# ip_phone_e_wifi.net
KiCad netlist of a schematic drawn in Altium Designer
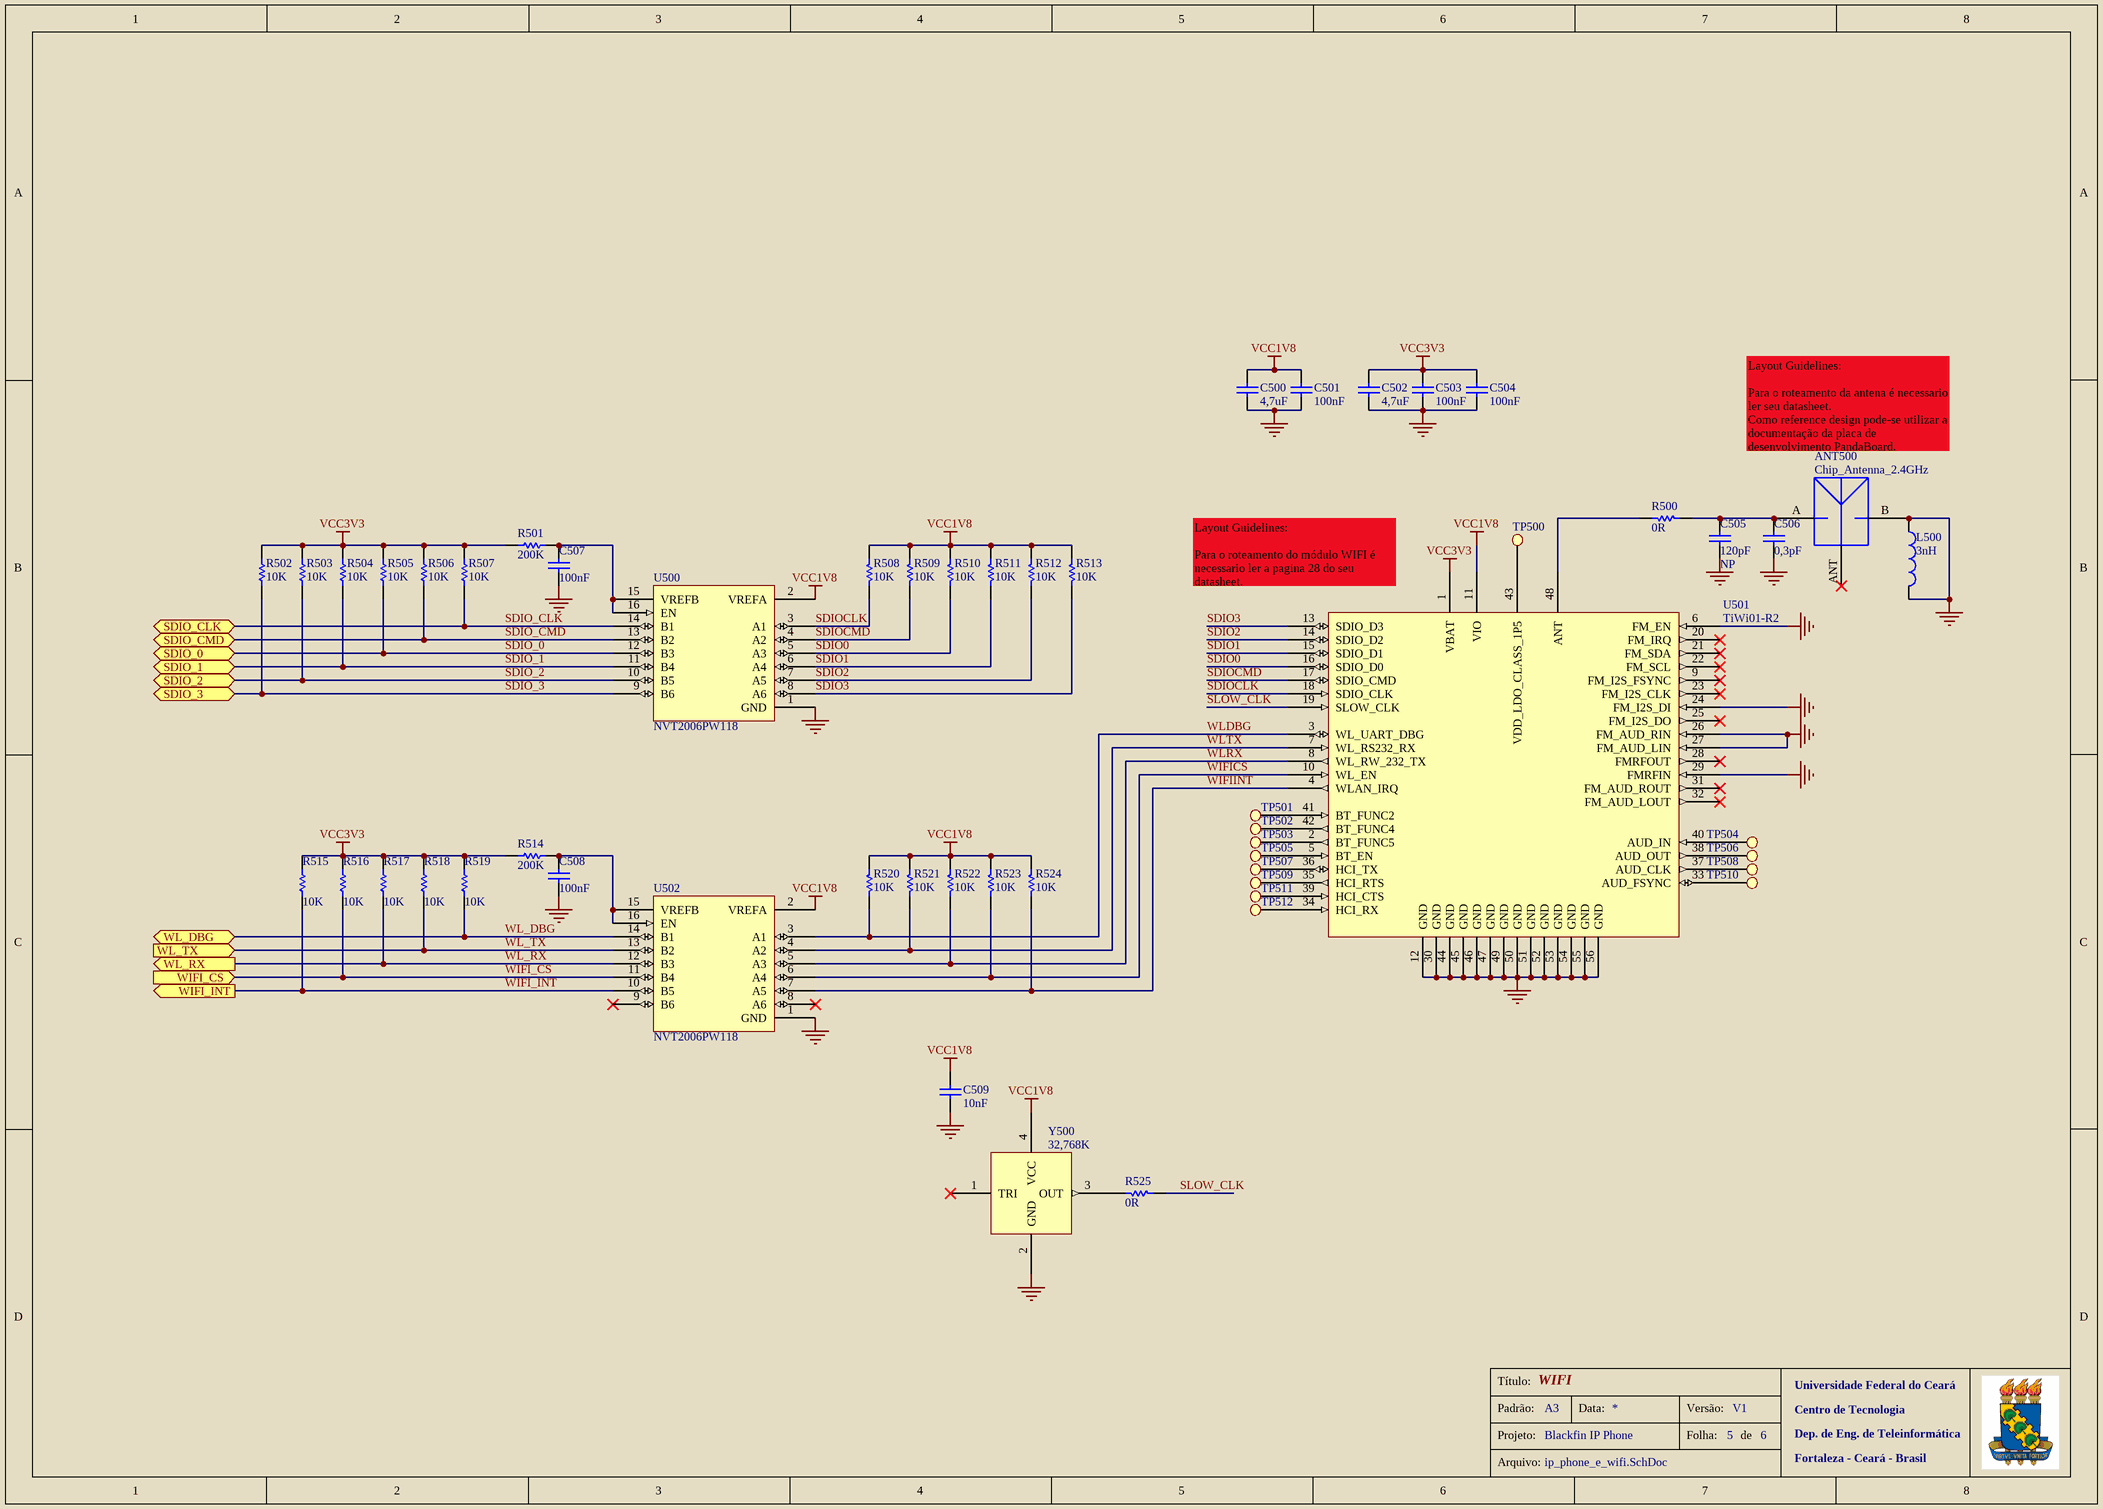
[diagram p0: ip_phone_e_wifi.SchDoc]

(export (version "E")
  (design (tool "Eeschema 10.0.6"))
  (components
    (comp (ref "ANT500")
      (value "Chip_Antenna_2.4GHz")
      (footprint "ip_phone:ANTENNA")
      (description "Antenna 2.4GHz Ceramic Chip SMD")
      (fields (field (name "MANUFACTURER") "TDK") (field (name "EVENDORPART#") "445-6134-1-ND"))
      (libsource (lib "ip_phone") (part "Antenna2_4GHzChip"))
    )
    (comp (ref "C500")
      (value "4,7uF")
      (footprint "ip_phone:CC1005-0402")
      (description "MLCC - SMD/SMT 4.7uF 20% 6.3Volts 0402")
      (fields (field (name "EVENDORPART#") "810-C1005X5R0J475M") (field (name "MANUFACTURER") "TDK"))
      (libsource (lib "ip_phone") (part "Capacitor"))
    )
    (comp (ref "C501")
      (value "100nF")
      (footprint "ip_phone:CC1005-0402")
      (description "MLCC - SMD/SMT 0.1UF 16V 10% 0402")
      (fields (field (name "EVENDORPART#") "810-C1005X7R1C104K") (field (name "MANUFACTURER") "TDK"))
      (libsource (lib "ip_phone") (part "Capacitor"))
    )
    (comp (ref "C502")
      (value "4,7uF")
      (footprint "ip_phone:CC1005-0402")
      (description "MLCC - SMD/SMT 4.7uF 20% 6.3Volts 0402")
      (fields (field (name "EVENDORPART#") "810-C1005X5R0J475M") (field (name "MANUFACTURER") "TDK"))
      (libsource (lib "ip_phone") (part "Capacitor"))
    )
    (comp (ref "C503")
      (value "100nF")
      (footprint "ip_phone:CC1005-0402")
      (description "MLCC - SMD/SMT 0.1UF 16V 10% 0402")
      (fields (field (name "EVENDORPART#") "810-C1005X7R1C104K") (field (name "MANUFACTURER") "TDK"))
      (libsource (lib "ip_phone") (part "Capacitor"))
    )
    (comp (ref "C504")
      (value "100nF")
      (footprint "ip_phone:CC1005-0402")
      (description "MLCC - SMD/SMT 0.1UF 16V 10% 0402")
      (fields (field (name "EVENDORPART#") "810-C1005X7R1C104K") (field (name "MANUFACTURER") "TDK"))
      (libsource (lib "ip_phone") (part "Capacitor"))
    )
    (comp (ref "C505")
      (value "120pF")
      (footprint "ip_phone:CC1005-0402_NP")
      (description "MLCC - SMD/SMT 0402 120pF 50volts C0G 5%")
      (fields
        (field (name "EVENDORPART#") "810-C1005C0G1H121J")
        (field (name "MANUFACTURER") "TDK")
        (field (name "NP") "NP")
      )
      (libsource (lib "ip_phone") (part "Capacitor"))
    )
    (comp (ref "C506")
      (value "0,3pF")
      (footprint "ip_phone:CC1005-0402")
      (description "MLCC - SMD/SMT 0.3pF 50Volts C0G 0.1pF")
      (fields (field (name "EVENDORPART#") "81-GRM1535C1HR30BD5D") (field (name "MANUFACTURER") "Murata"))
      (libsource (lib "ip_phone") (part "Capacitor"))
    )
    (comp (ref "C507")
      (value "100nF")
      (footprint "ip_phone:CC1005-0402")
      (description "MLCC - SMD/SMT 0.1UF 16V 10% 0402")
      (fields (field (name "EVENDORPART#") "810-C1005X7R1C104K") (field (name "MANUFACTURER") "TDK"))
      (libsource (lib "ip_phone") (part "Capacitor"))
    )
    (comp (ref "C508")
      (value "100nF")
      (footprint "ip_phone:CC1005-0402")
      (description "MLCC - SMD/SMT 0.1UF 16V 10% 0402")
      (fields (field (name "EVENDORPART#") "810-C1005X7R1C104K") (field (name "MANUFACTURER") "TDK"))
      (libsource (lib "ip_phone") (part "Capacitor"))
    )
    (comp (ref "C509")
      (value "10nF")
      (footprint "ip_phone:CC1005-0402")
      (description "Ceramic Capacitor 10nF 50V X7R 0402")
      (fields (field (name "EVENDORPART#") "810-C1005X7R1C103K") (field (name "MANUFACTURER") "TDK"))
      (libsource (lib "ip_phone") (part "Capacitor"))
    )
    (comp (ref "L500")
      (value "3nH")
      (footprint "ip_phone:INDUTOR_0402")
      (description "Inductor")
      (fields
        (field (name "EVENDORPART#") "712-1457-1-ND")
        (field (name "MANUFACTURER") "Johanson Technology Inc")
      )
      (libsource (lib "ip_phone") (part "Inductor"))
    )
    (comp (ref "R500")
      (value "0R")
      (footprint "ip_phone:CR1005-0402")
      (description "Thick Film Resistors 0402 1/16W Jumper")
      (fields
        (field (name "EVENDORPART#") "667-ERJ-2GE0R00X")
        (field (name "MANUFACTURER") "Panasonic Electronic Components")
      )
      (libsource (lib "ip_phone") (part "Resistor"))
    )
    (comp (ref "R501")
      (value "200K")
      (footprint "ip_phone:CR1005-0402")
      (description "Thick Film Resistors 1/16WATT 200K 0402")
      (fields (field (name "EVENDORPART#") "304-200K-RC") (field (name "MANUFACTURER") "Xicon"))
      (libsource (lib "ip_phone") (part "Resistor"))
    )
    (comp (ref "R502")
      (value "10K")
      (footprint "ip_phone:CR1005-0402")
      (description "Thick Film Resistors SMD 0402 10K 5%  1/16 W")
      (fields (field (name "EVENDORPART#") "311-10KJRCT-ND") (field (name "MANUFACTURER") "Yageo"))
      (libsource (lib "ip_phone") (part "Resistor"))
    )
    (comp (ref "R503")
      (value "10K")
      (footprint "ip_phone:CR1005-0402")
      (description "Thick Film Resistors SMD 0402 10K 5%  1/16 W")
      (fields (field (name "EVENDORPART#") "311-10KJRCT-ND") (field (name "MANUFACTURER") "Yageo"))
      (libsource (lib "ip_phone") (part "Resistor"))
    )
    (comp (ref "R504")
      (value "10K")
      (footprint "ip_phone:CR1005-0402")
      (description "Thick Film Resistors SMD 0402 10K 5%  1/16 W")
      (fields (field (name "EVENDORPART#") "311-10KJRCT-ND") (field (name "MANUFACTURER") "Yageo"))
      (libsource (lib "ip_phone") (part "Resistor"))
    )
    (comp (ref "R505")
      (value "10K")
      (footprint "ip_phone:CR1005-0402")
      (description "Thick Film Resistors SMD 0402 10K 5%  1/16 W")
      (fields (field (name "EVENDORPART#") "311-10KJRCT-ND") (field (name "MANUFACTURER") "Yageo"))
      (libsource (lib "ip_phone") (part "Resistor"))
    )
    (comp (ref "R506")
      (value "10K")
      (footprint "ip_phone:CR1005-0402")
      (description "Thick Film Resistors SMD 0402 10K 5%  1/16 W")
      (fields (field (name "EVENDORPART#") "311-10KJRCT-ND") (field (name "MANUFACTURER") "Yageo"))
      (libsource (lib "ip_phone") (part "Resistor"))
    )
    (comp (ref "R507")
      (value "10K")
      (footprint "ip_phone:CR1005-0402")
      (description "Thick Film Resistors SMD 0402 10K 5%  1/16 W")
      (fields (field (name "EVENDORPART#") "311-10KJRCT-ND") (field (name "MANUFACTURER") "Yageo"))
      (libsource (lib "ip_phone") (part "Resistor"))
    )
    (comp (ref "R508")
      (value "10K")
      (footprint "ip_phone:CR1005-0402")
      (description "Thick Film Resistors SMD 0402 10K 5%  1/16 W")
      (fields (field (name "EVENDORPART#") "311-10KJRCT-ND") (field (name "MANUFACTURER") "Yageo"))
      (libsource (lib "ip_phone") (part "Resistor"))
    )
    (comp (ref "R509")
      (value "10K")
      (footprint "ip_phone:CR1005-0402")
      (description "Thick Film Resistors SMD 0402 10K 5%  1/16 W")
      (fields (field (name "EVENDORPART#") "311-10KJRCT-ND") (field (name "MANUFACTURER") "Yageo"))
      (libsource (lib "ip_phone") (part "Resistor"))
    )
    (comp (ref "R510")
      (value "10K")
      (footprint "ip_phone:CR1005-0402")
      (description "Thick Film Resistors SMD 0402 10K 5%  1/16 W")
      (fields (field (name "EVENDORPART#") "311-10KJRCT-ND") (field (name "MANUFACTURER") "Yageo"))
      (libsource (lib "ip_phone") (part "Resistor"))
    )
    (comp (ref "R511")
      (value "10K")
      (footprint "ip_phone:CR1005-0402")
      (description "Thick Film Resistors SMD 0402 10K 5%  1/16 W")
      (fields (field (name "EVENDORPART#") "311-10KJRCT-ND") (field (name "MANUFACTURER") "Yageo"))
      (libsource (lib "ip_phone") (part "Resistor"))
    )
    (comp (ref "R512")
      (value "10K")
      (footprint "ip_phone:CR1005-0402")
      (description "Thick Film Resistors SMD 0402 10K 5%  1/16 W")
      (fields (field (name "EVENDORPART#") "311-10KJRCT-ND") (field (name "MANUFACTURER") "Yageo"))
      (libsource (lib "ip_phone") (part "Resistor"))
    )
    (comp (ref "R513")
      (value "10K")
      (footprint "ip_phone:CR1005-0402")
      (description "Thick Film Resistors SMD 0402 10K 5%  1/16 W")
      (fields (field (name "EVENDORPART#") "311-10KJRCT-ND") (field (name "MANUFACTURER") "Yageo"))
      (libsource (lib "ip_phone") (part "Resistor"))
    )
    (comp (ref "R514")
      (value "200K")
      (footprint "ip_phone:CR1005-0402")
      (description "Thick Film Resistors 1/16WATT 200K 0402")
      (fields (field (name "EVENDORPART#") "304-200K-RC") (field (name "MANUFACTURER") "Xicon"))
      (libsource (lib "ip_phone") (part "Resistor"))
    )
    (comp (ref "R515")
      (value "10K")
      (footprint "ip_phone:CR1005-0402")
      (description "Thick Film Resistors SMD 0402 10K 5%  1/16 W")
      (fields (field (name "EVENDORPART#") "311-10KJRCT-ND") (field (name "MANUFACTURER") "Yageo"))
      (libsource (lib "ip_phone") (part "Resistor"))
    )
    (comp (ref "R516")
      (value "10K")
      (footprint "ip_phone:CR1005-0402")
      (description "Thick Film Resistors SMD 0402 10K 5%  1/16 W")
      (fields (field (name "EVENDORPART#") "311-10KJRCT-ND") (field (name "MANUFACTURER") "Yageo"))
      (libsource (lib "ip_phone") (part "Resistor"))
    )
    (comp (ref "R517")
      (value "10K")
      (footprint "ip_phone:CR1005-0402")
      (description "Thick Film Resistors SMD 0402 10K 5%  1/16 W")
      (fields (field (name "EVENDORPART#") "311-10KJRCT-ND") (field (name "MANUFACTURER") "Yageo"))
      (libsource (lib "ip_phone") (part "Resistor"))
    )
    (comp (ref "R518")
      (value "10K")
      (footprint "ip_phone:CR1005-0402")
      (description "Thick Film Resistors SMD 0402 10K 5%  1/16 W")
      (fields (field (name "EVENDORPART#") "311-10KJRCT-ND") (field (name "MANUFACTURER") "Yageo"))
      (libsource (lib "ip_phone") (part "Resistor"))
    )
    (comp (ref "R519")
      (value "10K")
      (footprint "ip_phone:CR1005-0402")
      (description "Thick Film Resistors SMD 0402 10K 5%  1/16 W")
      (fields (field (name "EVENDORPART#") "311-10KJRCT-ND") (field (name "MANUFACTURER") "Yageo"))
      (libsource (lib "ip_phone") (part "Resistor"))
    )
    (comp (ref "R520")
      (value "10K")
      (footprint "ip_phone:CR1005-0402")
      (description "Thick Film Resistors SMD 0402 10K 5%  1/16 W")
      (fields (field (name "EVENDORPART#") "311-10KJRCT-ND") (field (name "MANUFACTURER") "Yageo"))
      (libsource (lib "ip_phone") (part "Resistor"))
    )
    (comp (ref "R521")
      (value "10K")
      (footprint "ip_phone:CR1005-0402")
      (description "Thick Film Resistors SMD 0402 10K 5%  1/16 W")
      (fields (field (name "EVENDORPART#") "311-10KJRCT-ND") (field (name "MANUFACTURER") "Yageo"))
      (libsource (lib "ip_phone") (part "Resistor"))
    )
    (comp (ref "R522")
      (value "10K")
      (footprint "ip_phone:CR1005-0402")
      (description "Thick Film Resistors SMD 0402 10K 5%  1/16 W")
      (fields (field (name "EVENDORPART#") "311-10KJRCT-ND") (field (name "MANUFACTURER") "Yageo"))
      (libsource (lib "ip_phone") (part "Resistor"))
    )
    (comp (ref "R523")
      (value "10K")
      (footprint "ip_phone:CR1005-0402")
      (description "Thick Film Resistors SMD 0402 10K 5%  1/16 W")
      (fields (field (name "EVENDORPART#") "311-10KJRCT-ND") (field (name "MANUFACTURER") "Yageo"))
      (libsource (lib "ip_phone") (part "Resistor"))
    )
    (comp (ref "R524")
      (value "10K")
      (footprint "ip_phone:CR1005-0402")
      (description "Thick Film Resistors SMD 0402 10K 5%  1/16 W")
      (fields (field (name "EVENDORPART#") "311-10KJRCT-ND") (field (name "MANUFACTURER") "Yageo"))
      (libsource (lib "ip_phone") (part "Resistor"))
    )
    (comp (ref "R525")
      (value "0R")
      (footprint "ip_phone:CR1005-0402")
      (description "Thick Film Resistors 0402 1/16W Jumper")
      (fields
        (field (name "EVENDORPART#") "667-ERJ-2GE0R00X")
        (field (name "MANUFACTURER") "Panasonic Electronic Components")
      )
      (libsource (lib "ip_phone") (part "Resistor"))
    )
    (comp (ref "TP500")
      (value "Test Point")
      (footprint "ip_phone:Test Point")
      (fields (field (name "EVENDORPART#") "NÃO SE APLICA"))
      (libsource (lib "ip_phone") (part "Test Point"))
    )
    (comp (ref "TP501")
      (value "Test Point")
      (footprint "ip_phone:Test Point")
      (fields (field (name "EVENDORPART#") "NÃO SE APLICA"))
      (libsource (lib "ip_phone") (part "Test Point"))
    )
    (comp (ref "TP502")
      (value "Test Point")
      (footprint "ip_phone:Test Point")
      (fields (field (name "EVENDORPART#") "NÃO SE APLICA"))
      (libsource (lib "ip_phone") (part "Test Point"))
    )
    (comp (ref "TP503")
      (value "Test Point")
      (footprint "ip_phone:Test Point")
      (fields (field (name "EVENDORPART#") "NÃO SE APLICA"))
      (libsource (lib "ip_phone") (part "Test Point"))
    )
    (comp (ref "TP504")
      (value "Test Point")
      (footprint "ip_phone:Test Point")
      (fields (field (name "EVENDORPART#") "NÃO SE APLICA"))
      (libsource (lib "ip_phone") (part "Test Point"))
    )
    (comp (ref "TP505")
      (value "Test Point")
      (footprint "ip_phone:Test Point")
      (fields (field (name "EVENDORPART#") "NÃO SE APLICA"))
      (libsource (lib "ip_phone") (part "Test Point"))
    )
    (comp (ref "TP506")
      (value "Test Point")
      (footprint "ip_phone:Test Point")
      (fields (field (name "EVENDORPART#") "NÃO SE APLICA"))
      (libsource (lib "ip_phone") (part "Test Point"))
    )
    (comp (ref "TP507")
      (value "Test Point")
      (footprint "ip_phone:Test Point")
      (fields (field (name "EVENDORPART#") "NÃO SE APLICA"))
      (libsource (lib "ip_phone") (part "Test Point"))
    )
    (comp (ref "TP508")
      (value "Test Point")
      (footprint "ip_phone:Test Point")
      (fields (field (name "EVENDORPART#") "NÃO SE APLICA"))
      (libsource (lib "ip_phone") (part "Test Point"))
    )
    (comp (ref "TP509")
      (value "Test Point")
      (footprint "ip_phone:Test Point")
      (fields (field (name "EVENDORPART#") "NÃO SE APLICA"))
      (libsource (lib "ip_phone") (part "Test Point"))
    )
    (comp (ref "TP510")
      (value "Test Point")
      (footprint "ip_phone:Test Point")
      (fields (field (name "EVENDORPART#") "NÃO SE APLICA"))
      (libsource (lib "ip_phone") (part "Test Point"))
    )
    (comp (ref "TP511")
      (value "Test Point")
      (footprint "ip_phone:Test Point")
      (fields (field (name "EVENDORPART#") "NÃO SE APLICA"))
      (libsource (lib "ip_phone") (part "Test Point"))
    )
    (comp (ref "TP512")
      (value "Test Point")
      (footprint "ip_phone:Test Point")
      (fields (field (name "EVENDORPART#") "NÃO SE APLICA"))
      (libsource (lib "ip_phone") (part "Test Point"))
    )
    (comp (ref "U500")
      (value "NVT2006PW118")
      (footprint "ip_phone:TSSOP16")
      (description "Translation - Voltage Levels +/-50mA 1.5ns 2.1-5V")
      (fields
        (field (name "EVENDORPART#") "771-NVT2006PW118")
        (field (name "MANUFACTURER") "NXP Semiconductors")
      )
      (libsource (lib "ip_phone") (part "NVT2006PW118"))
    )
    (comp (ref "U501")
      (value "TiWi01-R2")
      (footprint "ip_phone:WIFI_MODULE")
      (description "WiFi / 802.11 TiWi01-R2 Module with U.FL Connector")
      (fields (field (name "EVENDORPART#") "741-450-0037") (field (name "MANUFACTURER") "LS Research"))
      (libsource (lib "ip_phone") (part "TiWi01-R2"))
    )
    (comp (ref "U502")
      (value "NVT2006PW118")
      (footprint "ip_phone:TSSOP16")
      (description "Translation - Voltage Levels +/-50mA 1.5ns 2.1-5V")
      (fields
        (field (name "EVENDORPART#") "771-NVT2006PW118")
        (field (name "MANUFACTURER") "NXP Semiconductors")
      )
      (libsource (lib "ip_phone") (part "NVT2006PW118"))
    )
    (comp (ref "Y500")
      (value "32,768K")
      (footprint "ip_phone:OSCILLATOR_32K")
      (description "Standard Clock Oscillators 32.768KHz 1.8V -40C +85C 25ppm")
      (fields (field (name "EVENDORPART#") "815-ASEK2-32.7K-LRT") (field (name "MANUFACTURER") "Abracon"))
      (libsource (lib "ip_phone") (part "Oscillator_32K"))
    )
  )
  (nets
    (net (code "1") (name "/SDIO0") (class "Default")
      (node (ref "R510") (pin "1") (pinfunction "1_1") (pintype "passive"))
      (node (ref "U500") (pin "5") (pinfunction "A3_5") (pintype "bidirectional"))
      (node (ref "U501") (pin "16") (pinfunction "SDIO_D0_16") (pintype "bidirectional"))
    )
    (net (code "2") (name "/SDIO1") (class "Default")
      (node (ref "R511") (pin "1") (pinfunction "1_1") (pintype "passive"))
      (node (ref "U500") (pin "6") (pinfunction "A4_6") (pintype "bidirectional"))
      (node (ref "U501") (pin "15") (pinfunction "SDIO_D1_15") (pintype "bidirectional"))
    )
    (net (code "3") (name "/SDIO2") (class "Default")
      (node (ref "R512") (pin "1") (pinfunction "1_1") (pintype "passive"))
      (node (ref "U500") (pin "7") (pinfunction "A5_7") (pintype "bidirectional"))
      (node (ref "U501") (pin "14") (pinfunction "SDIO_D2_14") (pintype "bidirectional"))
    )
    (net (code "4") (name "/SDIO3") (class "Default")
      (node (ref "R513") (pin "1") (pinfunction "1_1") (pintype "passive"))
      (node (ref "U500") (pin "8") (pinfunction "A6_8") (pintype "bidirectional"))
      (node (ref "U501") (pin "13") (pinfunction "SDIO_D3_13") (pintype "bidirectional"))
    )
    (net (code "5") (name "/SDIOCLK") (class "Default")
      (node (ref "R508") (pin "1") (pinfunction "1_1") (pintype "passive"))
      (node (ref "U500") (pin "3") (pinfunction "A1_3") (pintype "bidirectional"))
      (node (ref "U501") (pin "18") (pinfunction "SDIO_CLK_18") (pintype "input"))
    )
    (net (code "6") (name "/SDIOCMD") (class "Default")
      (node (ref "R509") (pin "1") (pinfunction "1_1") (pintype "passive"))
      (node (ref "U500") (pin "4") (pinfunction "A2_4") (pintype "bidirectional"))
      (node (ref "U501") (pin "17") (pinfunction "SDIO_CMD_17") (pintype "bidirectional"))
    )
    (net (code "7") (name "/SDIO_0") (class "Default")
      (node (ref "R505") (pin "2") (pinfunction "2_2") (pintype "passive"))
      (node (ref "U500") (pin "12") (pinfunction "B3_12") (pintype "bidirectional"))
    )
    (net (code "8") (name "/SDIO_1") (class "Default")
      (node (ref "R504") (pin "2") (pinfunction "2_2") (pintype "passive"))
      (node (ref "U500") (pin "11") (pinfunction "B4_11") (pintype "bidirectional"))
    )
    (net (code "9") (name "/SDIO_2") (class "Default")
      (node (ref "R503") (pin "2") (pinfunction "2_2") (pintype "passive"))
      (node (ref "U500") (pin "10") (pinfunction "B5_10") (pintype "bidirectional"))
    )
    (net (code "10") (name "/SDIO_3") (class "Default")
      (node (ref "R502") (pin "2") (pinfunction "2_2") (pintype "passive"))
      (node (ref "U500") (pin "9") (pinfunction "B6_9") (pintype "bidirectional"))
    )
    (net (code "11") (name "/SDIO_CLK") (class "Default")
      (node (ref "R507") (pin "2") (pinfunction "2_2") (pintype "passive"))
      (node (ref "U500") (pin "14") (pinfunction "B1_14") (pintype "bidirectional"))
    )
    (net (code "12") (name "/SDIO_CMD") (class "Default")
      (node (ref "R506") (pin "2") (pinfunction "2_2") (pintype "passive"))
      (node (ref "U500") (pin "13") (pinfunction "B2_13") (pintype "bidirectional"))
    )
    (net (code "13") (name "/SLOW_CLK") (class "Default")
      (node (ref "R525") (pin "1") (pinfunction "1_1") (pintype "passive"))
      (node (ref "U501") (pin "19") (pinfunction "SLOW_CLK_19") (pintype "input"))
    )
    (net (code "14") (name "/WIFICS") (class "Default")
      (node (ref "R523") (pin "1") (pinfunction "1_1") (pintype "passive"))
      (node (ref "U501") (pin "10") (pinfunction "WL_EN_10") (pintype "input"))
      (node (ref "U502") (pin "6") (pinfunction "A4_6") (pintype "bidirectional"))
    )
    (net (code "15") (name "/WIFIINT") (class "Default")
      (node (ref "R524") (pin "1") (pinfunction "1_1") (pintype "passive"))
      (node (ref "U501") (pin "4") (pinfunction "WLAN_IRQ_4") (pintype "output"))
      (node (ref "U502") (pin "7") (pinfunction "A5_7") (pintype "bidirectional"))
    )
    (net (code "16") (name "/WIFI_CS") (class "Default")
      (node (ref "R516") (pin "1") (pinfunction "1_1") (pintype "passive"))
      (node (ref "U502") (pin "11") (pinfunction "B4_11") (pintype "bidirectional"))
    )
    (net (code "17") (name "/WIFI_INT") (class "Default")
      (node (ref "R515") (pin "1") (pinfunction "1_1") (pintype "passive"))
      (node (ref "U502") (pin "10") (pinfunction "B5_10") (pintype "bidirectional"))
    )
    (net (code "18") (name "/WLDBG") (class "Default")
      (node (ref "R520") (pin "1") (pinfunction "1_1") (pintype "passive"))
      (node (ref "U501") (pin "3") (pinfunction "WL_UART_DBG_3") (pintype "bidirectional"))
      (node (ref "U502") (pin "3") (pinfunction "A1_3") (pintype "bidirectional"))
    )
    (net (code "19") (name "/WLRX") (class "Default")
      (node (ref "R522") (pin "1") (pinfunction "1_1") (pintype "passive"))
      (node (ref "U501") (pin "8") (pinfunction "WL_RW_232_TX_8") (pintype "output"))
      (node (ref "U502") (pin "5") (pinfunction "A3_5") (pintype "bidirectional"))
    )
    (net (code "20") (name "/WLTX") (class "Default")
      (node (ref "R521") (pin "1") (pinfunction "1_1") (pintype "passive"))
      (node (ref "U501") (pin "7") (pinfunction "WL_RS232_RX_7") (pintype "input"))
      (node (ref "U502") (pin "4") (pinfunction "A2_4") (pintype "bidirectional"))
    )
    (net (code "21") (name "/WL_DBG") (class "Default")
      (node (ref "R519") (pin "1") (pinfunction "1_1") (pintype "passive"))
      (node (ref "U502") (pin "14") (pinfunction "B1_14") (pintype "bidirectional"))
    )
    (net (code "22") (name "/WL_RX") (class "Default")
      (node (ref "R517") (pin "1") (pinfunction "1_1") (pintype "passive"))
      (node (ref "U502") (pin "12") (pinfunction "B3_12") (pintype "bidirectional"))
    )
    (net (code "23") (name "/WL_TX") (class "Default")
      (node (ref "R518") (pin "1") (pinfunction "1_1") (pintype "passive"))
      (node (ref "U502") (pin "13") (pinfunction "B2_13") (pintype "bidirectional"))
    )
    (net (code "24") (name "GND") (class "Default")
      (node (ref "ANT500") (pin "B") (pinfunction "FIXINGELEC_B") (pintype "passive"))
      (node (ref "C500") (pin "2") (pinfunction "2_2") (pintype "passive"))
      (node (ref "C501") (pin "2") (pinfunction "2_2") (pintype "passive"))
      (node (ref "C502") (pin "2") (pinfunction "2_2") (pintype "passive"))
      (node (ref "C503") (pin "2") (pinfunction "2_2") (pintype "passive"))
      (node (ref "C504") (pin "2") (pinfunction "2_2") (pintype "passive"))
      (node (ref "C505") (pin "1") (pinfunction "1_1") (pintype "passive"))
      (node (ref "C506") (pin "1") (pinfunction "1_1") (pintype "passive"))
      (node (ref "C507") (pin "1") (pinfunction "1_1") (pintype "passive"))
      (node (ref "C508") (pin "1") (pinfunction "1_1") (pintype "passive"))
      (node (ref "C509") (pin "1") (pinfunction "1_1") (pintype "passive"))
      (node (ref "L500") (pin "1") (pinfunction "1_1") (pintype "passive"))
      (node (ref "L500") (pin "2") (pinfunction "2_2") (pintype "passive"))
      (node (ref "U500") (pin "1") (pinfunction "GND_1") (pintype "power_in"))
      (node (ref "U501") (pin "12") (pinfunction "GND_12") (pintype "power_in"))
      (node (ref "U501") (pin "24") (pinfunction "FM_I2S_DI_24") (pintype "input"))
      (node (ref "U501") (pin "26") (pinfunction "FM_AUD_RIN_26") (pintype "input"))
      (node (ref "U501") (pin "27") (pinfunction "FM_AUD_LIN_27") (pintype "input"))
      (node (ref "U501") (pin "29") (pinfunction "FMRFIN_29") (pintype "input"))
      (node (ref "U501") (pin "30") (pinfunction "GND_30") (pintype "power_in"))
      (node (ref "U501") (pin "44") (pinfunction "GND_44") (pintype "power_in"))
      (node (ref "U501") (pin "45") (pinfunction "GND_45") (pintype "power_in"))
      (node (ref "U501") (pin "46") (pinfunction "GND_46") (pintype "power_in"))
      (node (ref "U501") (pin "47") (pinfunction "GND_47") (pintype "power_in"))
      (node (ref "U501") (pin "49") (pinfunction "GND_49") (pintype "power_in"))
      (node (ref "U501") (pin "50") (pinfunction "GND_50") (pintype "power_in"))
      (node (ref "U501") (pin "51") (pinfunction "GND_51") (pintype "power_in"))
      (node (ref "U501") (pin "52") (pinfunction "GND_52") (pintype "power_in"))
      (node (ref "U501") (pin "53") (pinfunction "GND_53") (pintype "power_in"))
      (node (ref "U501") (pin "54") (pinfunction "GND_54") (pintype "power_in"))
      (node (ref "U501") (pin "55") (pinfunction "GND_55") (pintype "power_in"))
      (node (ref "U501") (pin "56") (pinfunction "GND_56") (pintype "power_in"))
      (node (ref "U501") (pin "6") (pinfunction "FM_EN_6") (pintype "input"))
      (node (ref "U502") (pin "1") (pinfunction "GND_1") (pintype "power_in"))
      (node (ref "Y500") (pin "2") (pinfunction "GND_2") (pintype "power_in"))
    )
    (net (code "25") (name "Net-(ANT500-FEEDPOINT)") (class "Default")
      (node (ref "ANT500") (pin "A") (pinfunction "FEEDPOINT_A") (pintype "passive"))
      (node (ref "C505") (pin "2") (pinfunction "2_2") (pintype "passive"))
      (node (ref "C506") (pin "2") (pinfunction "2_2") (pintype "passive"))
      (node (ref "R500") (pin "1") (pinfunction "1_1") (pintype "passive"))
    )
    (net (code "26") (name "Net-(U500-EN)") (class "Default")
      (node (ref "C507") (pin "2") (pinfunction "2_2") (pintype "passive"))
      (node (ref "R501") (pin "1") (pinfunction "1_1") (pintype "passive"))
      (node (ref "U500") (pin "15") (pinfunction "VREFB_15") (pintype "power_in"))
      (node (ref "U500") (pin "16") (pinfunction "EN_16") (pintype "input"))
    )
    (net (code "27") (name "Net-(U501-ANT)") (class "Default")
      (node (ref "R500") (pin "2") (pinfunction "2_2") (pintype "passive"))
      (node (ref "U501") (pin "48") (pinfunction "ANT_48") (pintype "passive"))
    )
    (net (code "28") (name "Net-(U501-AUD_CLK)") (class "Default")
      (node (ref "TP508") (pin "1") (pinfunction "1_1") (pintype "passive"))
      (node (ref "U501") (pin "37") (pinfunction "AUD_CLK_37") (pintype "output"))
    )
    (net (code "29") (name "Net-(U501-AUD_FSYNC)") (class "Default")
      (node (ref "TP510") (pin "1") (pinfunction "1_1") (pintype "passive"))
      (node (ref "U501") (pin "33") (pinfunction "AUD_FSYNC_33") (pintype "bidirectional"))
    )
    (net (code "30") (name "Net-(U501-AUD_IN)") (class "Default")
      (node (ref "TP504") (pin "1") (pinfunction "1_1") (pintype "passive"))
      (node (ref "U501") (pin "40") (pinfunction "AUD_IN_40") (pintype "input"))
    )
    (net (code "31") (name "Net-(U501-AUD_OUT)") (class "Default")
      (node (ref "TP506") (pin "1") (pinfunction "1_1") (pintype "passive"))
      (node (ref "U501") (pin "38") (pinfunction "AUD_OUT_38") (pintype "output"))
    )
    (net (code "32") (name "Net-(U501-BT_EN)") (class "Default")
      (node (ref "TP505") (pin "1") (pinfunction "1_1") (pintype "passive"))
      (node (ref "U501") (pin "5") (pinfunction "BT_EN_5") (pintype "input"))
    )
    (net (code "33") (name "Net-(U501-BT_FUNC2)") (class "Default")
      (node (ref "TP501") (pin "1") (pinfunction "1_1") (pintype "passive"))
      (node (ref "U501") (pin "41") (pinfunction "BT_FUNC2_41") (pintype "input"))
    )
    (net (code "34") (name "Net-(U501-BT_FUNC4)") (class "Default")
      (node (ref "TP502") (pin "1") (pinfunction "1_1") (pintype "passive"))
      (node (ref "U501") (pin "42") (pinfunction "BT_FUNC4_42") (pintype "output"))
    )
    (net (code "35") (name "Net-(U501-BT_FUNC5)") (class "Default")
      (node (ref "TP503") (pin "1") (pinfunction "1_1") (pintype "passive"))
      (node (ref "U501") (pin "2") (pinfunction "BT_FUNC5_2") (pintype "output"))
    )
    (net (code "36") (name "Net-(U501-HCI_CTS)") (class "Default")
      (node (ref "TP511") (pin "1") (pinfunction "1_1") (pintype "passive"))
      (node (ref "U501") (pin "39") (pinfunction "HCI_CTS_39") (pintype "input"))
    )
    (net (code "37") (name "Net-(U501-HCI_RTS)") (class "Default")
      (node (ref "TP509") (pin "1") (pinfunction "1_1") (pintype "passive"))
      (node (ref "U501") (pin "35") (pinfunction "HCI_RTS_35") (pintype "output"))
    )
    (net (code "38") (name "Net-(U501-HCI_RX)") (class "Default")
      (node (ref "TP512") (pin "1") (pinfunction "1_1") (pintype "passive"))
      (node (ref "U501") (pin "34") (pinfunction "HCI_RX_34") (pintype "input"))
    )
    (net (code "39") (name "Net-(U501-HCI_TX)") (class "Default")
      (node (ref "TP507") (pin "1") (pinfunction "1_1") (pintype "passive"))
      (node (ref "U501") (pin "36") (pinfunction "HCI_TX_36") (pintype "bidirectional"))
    )
    (net (code "40") (name "Net-(U501-VDD_LDO_CLASS_1P5)") (class "Default")
      (node (ref "TP500") (pin "1") (pinfunction "1_1") (pintype "passive"))
      (node (ref "U501") (pin "43") (pinfunction "VDD_LDO_CLASS_1P5_43") (pintype "passive"))
    )
    (net (code "41") (name "Net-(U502-EN)") (class "Default")
      (node (ref "C508") (pin "2") (pinfunction "2_2") (pintype "passive"))
      (node (ref "R514") (pin "1") (pinfunction "1_1") (pintype "passive"))
      (node (ref "U502") (pin "15") (pinfunction "VREFB_15") (pintype "power_in"))
      (node (ref "U502") (pin "16") (pinfunction "EN_16") (pintype "input"))
    )
    (net (code "42") (name "Net-(Y500-OUT)") (class "Default")
      (node (ref "R525") (pin "2") (pinfunction "2_2") (pintype "passive"))
      (node (ref "Y500") (pin "3") (pinfunction "OUT_3") (pintype "output"))
    )
    (net (code "43") (name "VCC1V8") (class "Default")
      (node (ref "C500") (pin "1") (pinfunction "1_1") (pintype "passive"))
      (node (ref "C501") (pin "1") (pinfunction "1_1") (pintype "passive"))
      (node (ref "C509") (pin "2") (pinfunction "2_2") (pintype "passive"))
      (node (ref "R508") (pin "2") (pinfunction "2_2") (pintype "passive"))
      (node (ref "R509") (pin "2") (pinfunction "2_2") (pintype "passive"))
      (node (ref "R510") (pin "2") (pinfunction "2_2") (pintype "passive"))
      (node (ref "R511") (pin "2") (pinfunction "2_2") (pintype "passive"))
      (node (ref "R512") (pin "2") (pinfunction "2_2") (pintype "passive"))
      (node (ref "R513") (pin "2") (pinfunction "2_2") (pintype "passive"))
      (node (ref "R520") (pin "2") (pinfunction "2_2") (pintype "passive"))
      (node (ref "R521") (pin "2") (pinfunction "2_2") (pintype "passive"))
      (node (ref "R522") (pin "2") (pinfunction "2_2") (pintype "passive"))
      (node (ref "R523") (pin "2") (pinfunction "2_2") (pintype "passive"))
      (node (ref "R524") (pin "2") (pinfunction "2_2") (pintype "passive"))
      (node (ref "U500") (pin "2") (pinfunction "VREFA_2") (pintype "power_in"))
      (node (ref "U501") (pin "11") (pinfunction "VIO_11") (pintype "power_in"))
      (node (ref "U502") (pin "2") (pinfunction "VREFA_2") (pintype "power_in"))
      (node (ref "Y500") (pin "4") (pinfunction "VCC_4") (pintype "power_in"))
    )
    (net (code "44") (name "VCC3V3") (class "Default")
      (node (ref "C502") (pin "1") (pinfunction "1_1") (pintype "passive"))
      (node (ref "C503") (pin "1") (pinfunction "1_1") (pintype "passive"))
      (node (ref "C504") (pin "1") (pinfunction "1_1") (pintype "passive"))
      (node (ref "R501") (pin "2") (pinfunction "2_2") (pintype "passive"))
      (node (ref "R502") (pin "1") (pinfunction "1_1") (pintype "passive"))
      (node (ref "R503") (pin "1") (pinfunction "1_1") (pintype "passive"))
      (node (ref "R504") (pin "1") (pinfunction "1_1") (pintype "passive"))
      (node (ref "R505") (pin "1") (pinfunction "1_1") (pintype "passive"))
      (node (ref "R506") (pin "1") (pinfunction "1_1") (pintype "passive"))
      (node (ref "R507") (pin "1") (pinfunction "1_1") (pintype "passive"))
      (node (ref "R514") (pin "2") (pinfunction "2_2") (pintype "passive"))
      (node (ref "R515") (pin "2") (pinfunction "2_2") (pintype "passive"))
      (node (ref "R516") (pin "2") (pinfunction "2_2") (pintype "passive"))
      (node (ref "R517") (pin "2") (pinfunction "2_2") (pintype "passive"))
      (node (ref "R518") (pin "2") (pinfunction "2_2") (pintype "passive"))
      (node (ref "R519") (pin "2") (pinfunction "2_2") (pintype "passive"))
      (node (ref "U501") (pin "1") (pinfunction "VBAT_1") (pintype "power_in"))
    )
    (net (code "45") (name "unconnected-(ANT500-ANTENNA-PadANT)") (class "Default")
      (node (ref "ANT500") (pin "ANT") (pinfunction "ANTENNA_ANT") (pintype "passive+no_connect"))
    )
    (net (code "46") (name "unconnected-(U501-FMRFOUT-Pad28)") (class "Default")
      (node (ref "U501") (pin "28") (pinfunction "FMRFOUT_28") (pintype "output+no_connect"))
    )
    (net (code "47") (name "unconnected-(U501-FM_AUD_LOUT-Pad32)") (class "Default")
      (node (ref "U501") (pin "32") (pinfunction "FM_AUD_LOUT_32") (pintype "output+no_connect"))
    )
    (net (code "48") (name "unconnected-(U501-FM_AUD_ROUT-Pad31)") (class "Default")
      (node (ref "U501") (pin "31") (pinfunction "FM_AUD_ROUT_31") (pintype "output+no_connect"))
    )
    (net (code "49") (name "unconnected-(U501-FM_I2S_CLK-Pad23)") (class "Default")
      (node (ref "U501") (pin "23") (pinfunction "FM_I2S_CLK_23") (pintype "output+no_connect"))
    )
    (net (code "50") (name "unconnected-(U501-FM_I2S_DO-Pad25)") (class "Default")
      (node (ref "U501") (pin "25") (pinfunction "FM_I2S_DO_25") (pintype "output+no_connect"))
    )
    (net (code "51") (name "unconnected-(U501-FM_I2S_FSYNC-Pad9)") (class "Default")
      (node (ref "U501") (pin "9") (pinfunction "FM_I2S_FSYNC_9") (pintype "output+no_connect"))
    )
    (net (code "52") (name "unconnected-(U501-FM_IRQ-Pad20)") (class "Default")
      (node (ref "U501") (pin "20") (pinfunction "FM_IRQ_20") (pintype "output+no_connect"))
    )
    (net (code "53") (name "unconnected-(U501-FM_SCL-Pad22)") (class "Default")
      (node (ref "U501") (pin "22") (pinfunction "FM_SCL_22") (pintype "output+no_connect"))
    )
    (net (code "54") (name "unconnected-(U501-FM_SDA-Pad21)") (class "Default")
      (node (ref "U501") (pin "21") (pinfunction "FM_SDA_21") (pintype "output+no_connect"))
    )
    (net (code "55") (name "unconnected-(U502-A6-Pad8)") (class "Default")
      (node (ref "U502") (pin "8") (pinfunction "A6_8") (pintype "bidirectional+no_connect"))
    )
    (net (code "56") (name "unconnected-(U502-B6-Pad9)") (class "Default")
      (node (ref "U502") (pin "9") (pinfunction "B6_9") (pintype "bidirectional+no_connect"))
    )
    (net (code "57") (name "unconnected-(Y500-TRI-Pad1)") (class "Default")
      (node (ref "Y500") (pin "1") (pinfunction "TRI_1") (pintype "passive+no_connect"))
    )
  )
)
